# IMX7S_CONNECTORS___IHM.net
KiCad netlist of a schematic drawn in Altium Designer
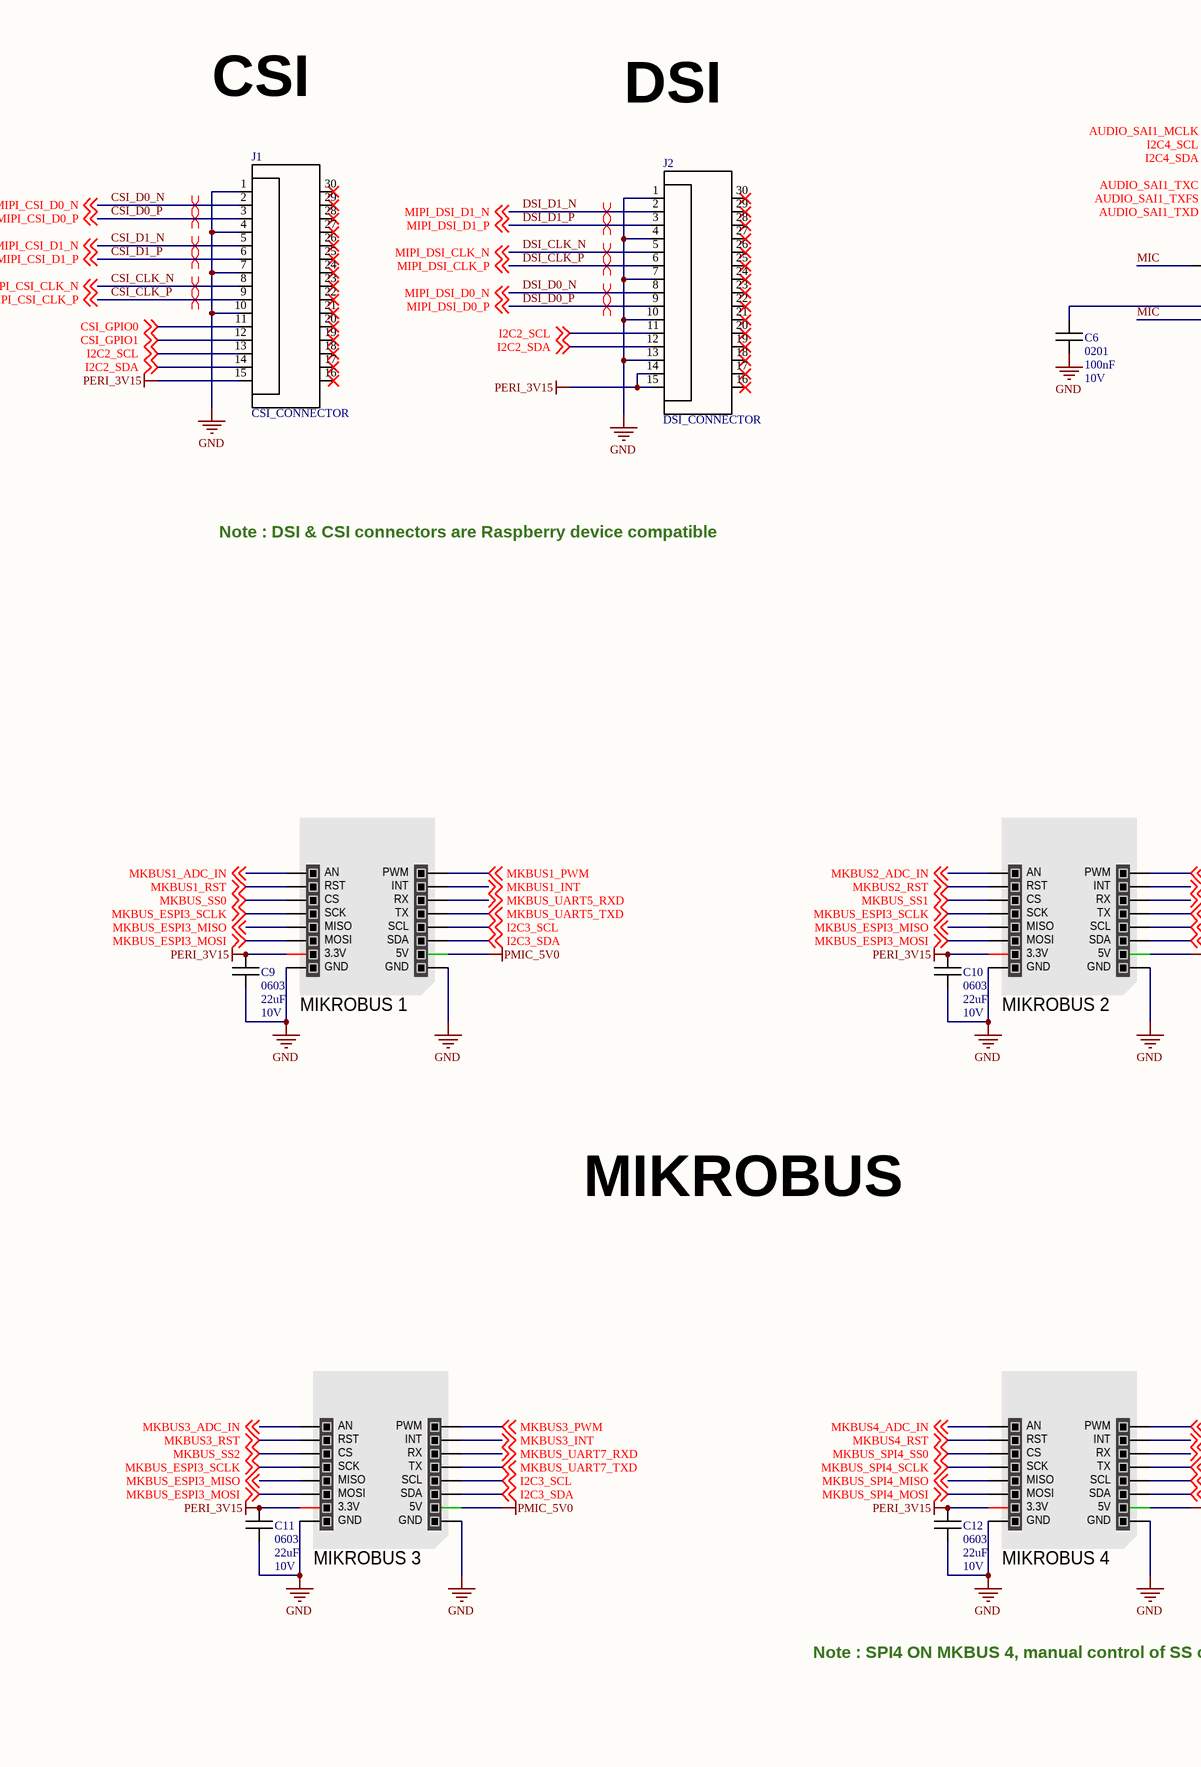
[diagram p0: IMX7S_CONNECTORS_&_IHM.SchDoc, left]
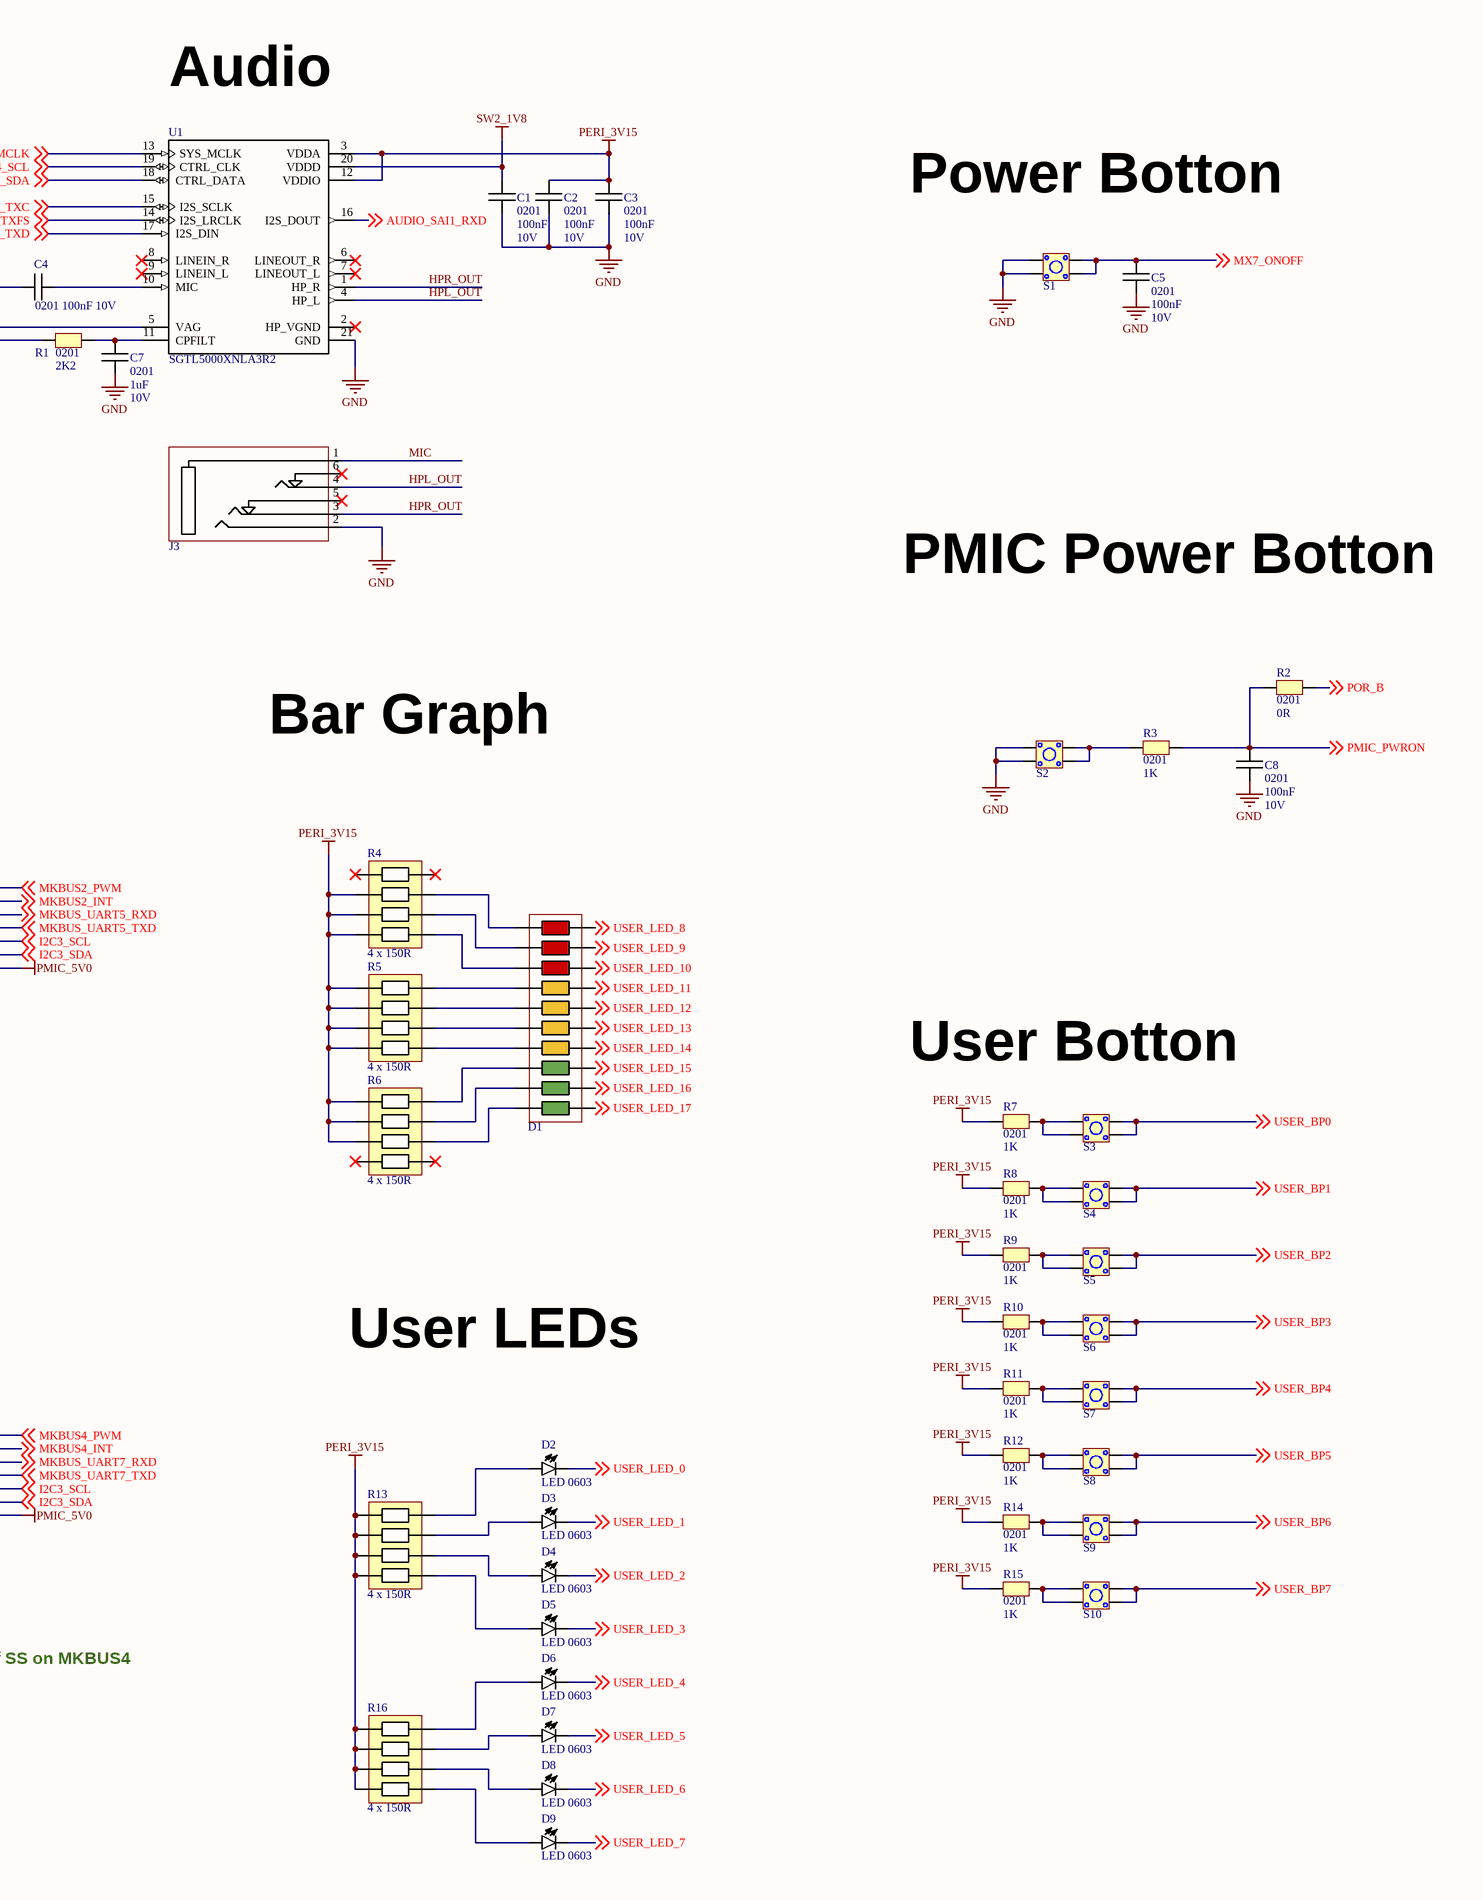
[diagram p1: IMX7S_CONNECTORS_&_IHM.SchDoc, right]

(export (version "E")
  (design (tool "Eeschema 10.0.6"))
  (components
    (comp (ref "C1")
      (value "100nF")
      (footprint "C0201")
      (description "CAP CER 0.1UF 10V X5R 0201")
      (fields
        (field (name "PACKAGE") "0201")
        (field (name "VOLTAGE") "10V")
        (field (name "TOLERANCE") "10%")
        (field (name "Comment") "C0201")
      )
      (libsource (lib "Schlib_IMX7") (part "C0201"))
    )
    (comp (ref "C2")
      (value "100nF")
      (footprint "C0201")
      (description "CAP CER 0.1UF 10V X5R 0201")
      (fields
        (field (name "PACKAGE") "0201")
        (field (name "VOLTAGE") "10V")
        (field (name "TOLERANCE") "10%")
        (field (name "Comment") "C0201")
      )
      (libsource (lib "Schlib_IMX7") (part "C0201"))
    )
    (comp (ref "C3")
      (value "100nF")
      (footprint "C0201")
      (description "CAP CER 0.1UF 10V X5R 0201")
      (fields
        (field (name "PACKAGE") "0201")
        (field (name "VOLTAGE") "10V")
        (field (name "TOLERANCE") "10%")
        (field (name "Comment") "C0201")
      )
      (libsource (lib "Schlib_IMX7") (part "C0201"))
    )
    (comp (ref "C4")
      (value "100nF")
      (footprint "C0201")
      (description "CAP CER 0.1UF 10V X5R 0201")
      (fields
        (field (name "PACKAGE") "0201")
        (field (name "VOLTAGE") "10V")
        (field (name "TOLERANCE") "10%")
        (field (name "Comment") "C0201")
      )
      (libsource (lib "Schlib_IMX7") (part "C0201"))
    )
    (comp (ref "C5")
      (value "100nF")
      (footprint "C0201")
      (description "CAP CER 0.1UF 10V X5R 0201")
      (fields
        (field (name "PACKAGE") "0201")
        (field (name "VOLTAGE") "10V")
        (field (name "TOLERANCE") "10%")
        (field (name "Comment") "C0201")
      )
      (libsource (lib "Schlib_IMX7") (part "C0201"))
    )
    (comp (ref "C6")
      (value "100nF")
      (footprint "C0201")
      (description "CAP CER 0.1UF 10V X5R 0201")
      (fields
        (field (name "PACKAGE") "0201")
        (field (name "VOLTAGE") "10V")
        (field (name "TOLERANCE") "10%")
        (field (name "Comment") "C0201")
      )
      (libsource (lib "Schlib_IMX7") (part "C0201"))
    )
    (comp (ref "C7")
      (value "1uF")
      (footprint "C0201")
      (description "CAP CER 1UF 6.3V X5R 0201")
      (fields
        (field (name "PACKAGE") "0201")
        (field (name "VOLTAGE") "10V")
        (field (name "TOLERANCE") "20%")
        (field (name "Comment") "C0201")
      )
      (libsource (lib "Schlib_IMX7") (part "C0201"))
    )
    (comp (ref "C8")
      (value "100nF")
      (footprint "C0201")
      (description "CAP CER 0.1UF 10V X5R 0201")
      (fields
        (field (name "PACKAGE") "0201")
        (field (name "VOLTAGE") "10V")
        (field (name "TOLERANCE") "10%")
        (field (name "Comment") "C0201")
      )
      (libsource (lib "Schlib_IMX7") (part "C0201"))
    )
    (comp (ref "C9")
      (value "22uF")
      (footprint "C0603")
      (description "Cap Ceramic 22uF 6.3V X5R 20% SMD 0603 85C Paper T/R")
      (fields
        (field (name "PACKAGE") "0603")
        (field (name "VOLTAGE") "10V")
        (field (name "TOLERANCE") "20%")
        (field (name "Comment") "C0603")
      )
      (libsource (lib "Schlib_IMX7") (part "C0603"))
    )
    (comp (ref "C10")
      (value "22uF")
      (footprint "C0603")
      (description "Cap Ceramic 22uF 6.3V X5R 20% SMD 0603 85C Paper T/R")
      (fields
        (field (name "PACKAGE") "0603")
        (field (name "VOLTAGE") "10V")
        (field (name "TOLERANCE") "20%")
        (field (name "Comment") "C0603")
      )
      (libsource (lib "Schlib_IMX7") (part "C0603"))
    )
    (comp (ref "C11")
      (value "22uF")
      (footprint "C0603")
      (description "Cap Ceramic 22uF 6.3V X5R 20% SMD 0603 85C Paper T/R")
      (fields
        (field (name "PACKAGE") "0603")
        (field (name "VOLTAGE") "10V")
        (field (name "TOLERANCE") "20%")
        (field (name "Comment") "C0603")
      )
      (libsource (lib "Schlib_IMX7") (part "C0603"))
    )
    (comp (ref "C12")
      (value "22uF")
      (footprint "C0603")
      (description "Cap Ceramic 22uF 6.3V X5R 20% SMD 0603 85C Paper T/R")
      (fields
        (field (name "PACKAGE") "0603")
        (field (name "VOLTAGE") "10V")
        (field (name "TOLERANCE") "20%")
        (field (name "Comment") "C0603")
      )
      (libsource (lib "Schlib_IMX7") (part "C0603"))
    )
    (comp (ref "D1")
      (value "BARGRAPH")
      (footprint "BARGRAPH")
      (description "BAR GRAPH, 10LED, GREEN/YEL/RED - More Details")
      (libsource (lib "Schlib_IMX7") (part "BARGRAPH"))
    )
    (comp (ref "D2")
      (value "LED 0603")
      (footprint "D0603")
      (description "LED RED DIFFUSED 0603 SMD")
      (libsource (lib "Schlib_IMX7") (part "LED"))
    )
    (comp (ref "D3")
      (value "LED 0603")
      (footprint "D0603")
      (description "LED RED DIFFUSED 0603 SMD")
      (libsource (lib "Schlib_IMX7") (part "LED"))
    )
    (comp (ref "D4")
      (value "LED 0603")
      (footprint "D0603")
      (description "LED RED DIFFUSED 0603 SMD")
      (libsource (lib "Schlib_IMX7") (part "LED"))
    )
    (comp (ref "D5")
      (value "LED 0603")
      (footprint "D0603")
      (description "LED RED DIFFUSED 0603 SMD")
      (libsource (lib "Schlib_IMX7") (part "LED"))
    )
    (comp (ref "D6")
      (value "LED 0603")
      (footprint "D0603")
      (description "LED RED DIFFUSED 0603 SMD")
      (libsource (lib "Schlib_IMX7") (part "LED"))
    )
    (comp (ref "D7")
      (value "LED 0603")
      (footprint "D0603")
      (description "LED RED DIFFUSED 0603 SMD")
      (libsource (lib "Schlib_IMX7") (part "LED"))
    )
    (comp (ref "D8")
      (value "LED 0603")
      (footprint "D0603")
      (description "LED RED DIFFUSED 0603 SMD")
      (libsource (lib "Schlib_IMX7") (part "LED"))
    )
    (comp (ref "D9")
      (value "LED 0603")
      (footprint "D0603")
      (description "LED RED DIFFUSED 0603 SMD")
      (libsource (lib "Schlib_IMX7") (part "LED"))
    )
    (comp (ref "J1")
      (value "CSI_CONNECTOR")
      (footprint "CSI_DSI")
      (libsource (lib "Schlib_IMX7") (part "CSI_DSI_CONN"))
    )
    (comp (ref "J2")
      (value "DSI_CONNECTOR")
      (footprint "CSI_DSI")
      (libsource (lib "Schlib_IMX7") (part "CSI_DSI_CONN"))
    )
    (comp (ref "J3")
      (value "JACK_AUDIO")
      (footprint "JACK_AUDIO")
      (libsource (lib "Schlib_IMX7") (part "JACK_AUDIO"))
    )
    (comp (ref "MIKROBUS 1")
      (value "MIKROBUS HOST CONN.")
      (footprint "MIKROBUS HOST CONN.")
      (description "mikroBUS Host Socket")
      (libsource (lib "Schlib_IMX7") (part "MIKROBUS HOST CONN._1"))
    )
    (comp (ref "MIKROBUS 2")
      (value "MIKROBUS HOST CONN.")
      (footprint "MIKROBUS HOST CONN.")
      (description "mikroBUS Host Socket")
      (libsource (lib "Schlib_IMX7") (part "MIKROBUS HOST CONN._1"))
    )
    (comp (ref "MIKROBUS 3")
      (value "MIKROBUS HOST CONN.")
      (footprint "MIKROBUS HOST CONN.")
      (description "mikroBUS Host Socket")
      (libsource (lib "Schlib_IMX7") (part "MIKROBUS HOST CONN._1"))
    )
    (comp (ref "MIKROBUS 4")
      (value "MIKROBUS HOST CONN.")
      (footprint "MIKROBUS HOST CONN.")
      (description "mikroBUS Host Socket")
      (libsource (lib "Schlib_IMX7") (part "MIKROBUS HOST CONN._1"))
    )
    (comp (ref "R1")
      (value "2K2")
      (footprint "R0201")
      (description "RESISTOR, 0201, 0.05W, 1%, 2K2")
      (fields (field (name "PACKAGE") "0201") (field (name "VOLTAGE") "0V") (field (name "TOLERANCE") "1%"))
      (libsource (lib "Schlib_IMX7") (part "R0201"))
    )
    (comp (ref "R2")
      (value "0R")
      (footprint "R0201")
      (description "RES SMD 0 OHM JUMPER 1/20W 0201")
      (fields (field (name "PACKAGE") "0201") (field (name "VOLTAGE") "0V") (field (name "TOLERANCE") "5%"))
      (libsource (lib "Schlib_IMX7") (part "R0201"))
    )
    (comp (ref "R3")
      (value "1K")
      (footprint "R0201")
      (description "RES SMD 1K OHM 1% 1/20W 0201")
      (fields (field (name "PACKAGE") "0201") (field (name "VOLTAGE") "0V") (field (name "TOLERANCE") "1%"))
      (libsource (lib "Schlib_IMX7") (part "R0201"))
    )
    (comp (ref "R4")
      (value "4 x 150R")
      (footprint "Reseau_R_1206")
      (fields (field (name "TOLERANCE") "5%"))
      (libsource (lib "Schlib_IMX7") (part "Reseau_res"))
    )
    (comp (ref "R5")
      (value "4 x 150R")
      (footprint "Reseau_R_1206")
      (fields (field (name "TOLERANCE") "5%"))
      (libsource (lib "Schlib_IMX7") (part "Reseau_res"))
    )
    (comp (ref "R6")
      (value "4 x 150R")
      (footprint "Reseau_R_1206")
      (fields (field (name "TOLERANCE") "5%"))
      (libsource (lib "Schlib_IMX7") (part "Reseau_res"))
    )
    (comp (ref "R7")
      (value "1K")
      (footprint "R0201")
      (description "RES SMD 1K OHM 1% 1/20W 0201")
      (fields (field (name "PACKAGE") "0201") (field (name "VOLTAGE") "0V") (field (name "TOLERANCE") "1%"))
      (libsource (lib "Schlib_IMX7") (part "R0201"))
    )
    (comp (ref "R8")
      (value "1K")
      (footprint "R0201")
      (description "RES SMD 1K OHM 1% 1/20W 0201")
      (fields (field (name "PACKAGE") "0201") (field (name "VOLTAGE") "0V") (field (name "TOLERANCE") "1%"))
      (libsource (lib "Schlib_IMX7") (part "R0201"))
    )
    (comp (ref "R9")
      (value "1K")
      (footprint "R0201")
      (description "RES SMD 1K OHM 1% 1/20W 0201")
      (fields (field (name "PACKAGE") "0201") (field (name "VOLTAGE") "0V") (field (name "TOLERANCE") "1%"))
      (libsource (lib "Schlib_IMX7") (part "R0201"))
    )
    (comp (ref "R10")
      (value "1K")
      (footprint "R0201")
      (description "RES SMD 1K OHM 1% 1/20W 0201")
      (fields (field (name "PACKAGE") "0201") (field (name "VOLTAGE") "0V") (field (name "TOLERANCE") "1%"))
      (libsource (lib "Schlib_IMX7") (part "R0201"))
    )
    (comp (ref "R11")
      (value "1K")
      (footprint "R0201")
      (description "RES SMD 1K OHM 1% 1/20W 0201")
      (fields (field (name "PACKAGE") "0201") (field (name "VOLTAGE") "0V") (field (name "TOLERANCE") "1%"))
      (libsource (lib "Schlib_IMX7") (part "R0201"))
    )
    (comp (ref "R12")
      (value "1K")
      (footprint "R0201")
      (description "RES SMD 1K OHM 1% 1/20W 0201")
      (fields (field (name "PACKAGE") "0201") (field (name "VOLTAGE") "0V") (field (name "TOLERANCE") "1%"))
      (libsource (lib "Schlib_IMX7") (part "R0201"))
    )
    (comp (ref "R13")
      (value "4 x 150R")
      (footprint "Reseau_R_1206")
      (fields (field (name "TOLERANCE") "5%"))
      (libsource (lib "Schlib_IMX7") (part "Reseau_res"))
    )
    (comp (ref "R14")
      (value "1K")
      (footprint "R0201")
      (description "RES SMD 1K OHM 1% 1/20W 0201")
      (fields (field (name "PACKAGE") "0201") (field (name "VOLTAGE") "0V") (field (name "TOLERANCE") "1%"))
      (libsource (lib "Schlib_IMX7") (part "R0201"))
    )
    (comp (ref "R15")
      (value "1K")
      (footprint "R0201")
      (description "RES SMD 1K OHM 1% 1/20W 0201")
      (fields (field (name "PACKAGE") "0201") (field (name "VOLTAGE") "0V") (field (name "TOLERANCE") "1%"))
      (libsource (lib "Schlib_IMX7") (part "R0201"))
    )
    (comp (ref "R16")
      (value "4 x 150R")
      (footprint "Reseau_R_1206")
      (fields (field (name "TOLERANCE") "5%"))
      (libsource (lib "Schlib_IMX7") (part "Reseau_res"))
    )
    (comp (ref "S1")
      (value "BP")
      (footprint "BP")
      (description "Switch Tactile N.O. SPST Round Button Gull Wing 0.05A 12VDC 100000Cycles 1.6N SMD T/R")
      (fields
        (field (name "MANUFACTURER") "TE Connectivity (Tyco Electronics)")
        (field (name "MANUFACTURER PART NUMBER") "1-1825027-4")
      )
      (libsource (lib "Schlib_IMX7") (part "BP"))
    )
    (comp (ref "S2")
      (value "BP")
      (footprint "BP")
      (description "Switch Tactile N.O. SPST Round Button Gull Wing 0.05A 12VDC 100000Cycles 1.6N SMD T/R")
      (fields
        (field (name "MANUFACTURER") "TE Connectivity (Tyco Electronics)")
        (field (name "MANUFACTURER PART NUMBER") "1-1825027-4")
      )
      (libsource (lib "Schlib_IMX7") (part "BP"))
    )
    (comp (ref "S3")
      (value "BP")
      (footprint "BP")
      (description "Switch Tactile N.O. SPST Round Button Gull Wing 0.05A 12VDC 100000Cycles 1.6N SMD T/R")
      (fields
        (field (name "MANUFACTURER") "TE Connectivity (Tyco Electronics)")
        (field (name "MANUFACTURER PART NUMBER") "1-1825027-4")
      )
      (libsource (lib "Schlib_IMX7") (part "BP"))
    )
    (comp (ref "S4")
      (value "BP")
      (footprint "BP")
      (description "Switch Tactile N.O. SPST Round Button Gull Wing 0.05A 12VDC 100000Cycles 1.6N SMD T/R")
      (fields
        (field (name "MANUFACTURER") "TE Connectivity (Tyco Electronics)")
        (field (name "MANUFACTURER PART NUMBER") "1-1825027-4")
      )
      (libsource (lib "Schlib_IMX7") (part "BP"))
    )
    (comp (ref "S5")
      (value "BP")
      (footprint "BP")
      (description "Switch Tactile N.O. SPST Round Button Gull Wing 0.05A 12VDC 100000Cycles 1.6N SMD T/R")
      (fields
        (field (name "MANUFACTURER") "TE Connectivity (Tyco Electronics)")
        (field (name "MANUFACTURER PART NUMBER") "1-1825027-4")
      )
      (libsource (lib "Schlib_IMX7") (part "BP"))
    )
    (comp (ref "S6")
      (value "BP")
      (footprint "BP")
      (description "Switch Tactile N.O. SPST Round Button Gull Wing 0.05A 12VDC 100000Cycles 1.6N SMD T/R")
      (fields
        (field (name "MANUFACTURER") "TE Connectivity (Tyco Electronics)")
        (field (name "MANUFACTURER PART NUMBER") "1-1825027-4")
      )
      (libsource (lib "Schlib_IMX7") (part "BP"))
    )
    (comp (ref "S7")
      (value "BP")
      (footprint "BP")
      (description "Switch Tactile N.O. SPST Round Button Gull Wing 0.05A 12VDC 100000Cycles 1.6N SMD T/R")
      (fields
        (field (name "MANUFACTURER") "TE Connectivity (Tyco Electronics)")
        (field (name "MANUFACTURER PART NUMBER") "1-1825027-4")
      )
      (libsource (lib "Schlib_IMX7") (part "BP"))
    )
    (comp (ref "S8")
      (value "BP")
      (footprint "BP")
      (description "Switch Tactile N.O. SPST Round Button Gull Wing 0.05A 12VDC 100000Cycles 1.6N SMD T/R")
      (fields
        (field (name "MANUFACTURER") "TE Connectivity (Tyco Electronics)")
        (field (name "MANUFACTURER PART NUMBER") "1-1825027-4")
      )
      (libsource (lib "Schlib_IMX7") (part "BP"))
    )
    (comp (ref "S9")
      (value "BP")
      (footprint "BP")
      (description "Switch Tactile N.O. SPST Round Button Gull Wing 0.05A 12VDC 100000Cycles 1.6N SMD T/R")
      (fields
        (field (name "MANUFACTURER") "TE Connectivity (Tyco Electronics)")
        (field (name "MANUFACTURER PART NUMBER") "1-1825027-4")
      )
      (libsource (lib "Schlib_IMX7") (part "BP"))
    )
    (comp (ref "S10")
      (value "BP")
      (footprint "BP")
      (description "Switch Tactile N.O. SPST Round Button Gull Wing 0.05A 12VDC 100000Cycles 1.6N SMD T/R")
      (fields
        (field (name "MANUFACTURER") "TE Connectivity (Tyco Electronics)")
        (field (name "MANUFACTURER PART NUMBER") "1-1825027-4")
      )
      (libsource (lib "Schlib_IMX7") (part "BP"))
    )
    (comp (ref "U1")
      (value "SGTL5000XNLA3R2")
      (footprint "QFN40P300X300X60-21N")
      (description "Audio Codec , Ultra Low-Power, 4 mw for DAC-to-HP, 98 dB SNR and -80 dB THD+N, QFN 32, Reel")
      (fields (field (name "DIGI-KEY_PART_NUMBER") "568-13255-1-ND") (field (name "MF") "NXP USA"))
      (libsource (lib "Schlib_IMX7") (part "SGTL5000XNLA3R2"))
    )
  )
  (nets
    (net (code "1") (name "/HPL_OUT") (class "Default")
      (node (ref "J3") (pin "4") (pintype "passive"))
      (node (ref "U1") (pin "4") (pinfunction "HP_L_4") (pintype "output"))
    )
    (net (code "2") (name "/HPR_OUT") (class "Default")
      (node (ref "J3") (pin "3") (pintype "passive"))
      (node (ref "U1") (pin "1") (pinfunction "HP_R_1") (pintype "output"))
    )
    (net (code "3") (name "/MIC") (class "Default")
      (node (ref "C4") (pin "1") (pinfunction "1_1") (pintype "passive"))
      (node (ref "J3") (pin "1") (pintype "passive"))
      (node (ref "R1") (pin "1") (pinfunction "1_1") (pintype "passive"))
    )
    (net (code "4") (name "AUDIO_SAI1_MCLK") (class "Default")
      (node (ref "U1") (pin "13") (pinfunction "SYS_MCLK_13") (pintype "input"))
    )
    (net (code "5") (name "AUDIO_SAI1_RXD") (class "Default")
      (node (ref "U1") (pin "16") (pinfunction "I2S_DOUT_16") (pintype "output"))
    )
    (net (code "6") (name "AUDIO_SAI1_TXC") (class "Default")
      (node (ref "U1") (pin "15") (pinfunction "I2S_SCLK_15") (pintype "bidirectional"))
    )
    (net (code "7") (name "AUDIO_SAI1_TXD") (class "Default")
      (node (ref "U1") (pin "17") (pinfunction "I2S_DIN_17") (pintype "input"))
    )
    (net (code "8") (name "AUDIO_SAI1_TXFS") (class "Default")
      (node (ref "U1") (pin "14") (pinfunction "I2S_LRCLK_14") (pintype "bidirectional"))
    )
    (net (code "9") (name "CSI_GPIO0") (class "Default")
      (node (ref "J1") (pin "11") (pinfunction "11_11") (pintype "passive"))
    )
    (net (code "10") (name "CSI_GPIO1") (class "Default")
      (node (ref "J1") (pin "12") (pinfunction "12_12") (pintype "passive"))
    )
    (net (code "11") (name "GND") (class "Default")
      (node (ref "C1") (pin "1") (pinfunction "1_1") (pintype "passive"))
      (node (ref "C10") (pin "1") (pinfunction "1_1") (pintype "passive"))
      (node (ref "C11") (pin "1") (pinfunction "1_1") (pintype "passive"))
      (node (ref "C12") (pin "1") (pinfunction "1_1") (pintype "passive"))
      (node (ref "C2") (pin "1") (pinfunction "1_1") (pintype "passive"))
      (node (ref "C3") (pin "1") (pinfunction "1_1") (pintype "passive"))
      (node (ref "C5") (pin "1") (pinfunction "1_1") (pintype "passive"))
      (node (ref "C6") (pin "1") (pinfunction "1_1") (pintype "passive"))
      (node (ref "C7") (pin "1") (pinfunction "1_1") (pintype "passive"))
      (node (ref "C8") (pin "1") (pinfunction "1_1") (pintype "passive"))
      (node (ref "C9") (pin "1") (pinfunction "1_1") (pintype "passive"))
      (node (ref "J1") (pin "1") (pinfunction "1_1") (pintype "passive"))
      (node (ref "J1") (pin "10") (pinfunction "10_10") (pintype "passive"))
      (node (ref "J1") (pin "4") (pinfunction "4_4") (pintype "passive"))
      (node (ref "J1") (pin "7") (pinfunction "7_7") (pintype "passive"))
      (node (ref "J2") (pin "1") (pinfunction "1_1") (pintype "passive"))
      (node (ref "J2") (pin "10") (pinfunction "10_10") (pintype "passive"))
      (node (ref "J2") (pin "13") (pinfunction "13_13") (pintype "passive"))
      (node (ref "J2") (pin "4") (pinfunction "4_4") (pintype "passive"))
      (node (ref "J2") (pin "7") (pinfunction "7_7") (pintype "passive"))
      (node (ref "J3") (pin "2") (pintype "passive"))
      (node (ref "MIKROBUS 1") (pin "8") (pinfunction "GND_8") (pintype "passive"))
      (node (ref "MIKROBUS 1") (pin "9") (pinfunction "GND_9") (pintype "passive"))
      (node (ref "MIKROBUS 2") (pin "8") (pinfunction "GND_8") (pintype "passive"))
      (node (ref "MIKROBUS 2") (pin "9") (pinfunction "GND_9") (pintype "passive"))
      (node (ref "MIKROBUS 3") (pin "8") (pinfunction "GND_8") (pintype "passive"))
      (node (ref "MIKROBUS 3") (pin "9") (pinfunction "GND_9") (pintype "passive"))
      (node (ref "MIKROBUS 4") (pin "8") (pinfunction "GND_8") (pintype "passive"))
      (node (ref "MIKROBUS 4") (pin "9") (pinfunction "GND_9") (pintype "passive"))
      (node (ref "S1") (pin "1") (pinfunction "1_1") (pintype "passive"))
      (node (ref "S1") (pin "2") (pinfunction "2_2") (pintype "passive"))
      (node (ref "S2") (pin "1") (pinfunction "1_1") (pintype "passive"))
      (node (ref "S2") (pin "2") (pinfunction "2_2") (pintype "passive"))
      (node (ref "U1") (pin "21") (pinfunction "GND_21") (pintype "power_in"))
    )
    (net (code "12") (name "I2C2_SCL") (class "Default")
      (node (ref "J1") (pin "13") (pinfunction "13_13") (pintype "passive"))
      (node (ref "J2") (pin "11") (pinfunction "11_11") (pintype "passive"))
    )
    (net (code "13") (name "I2C2_SDA") (class "Default")
      (node (ref "J1") (pin "14") (pinfunction "14_14") (pintype "passive"))
      (node (ref "J2") (pin "12") (pinfunction "12_12") (pintype "passive"))
    )
    (net (code "14") (name "I2C3_SCL") (class "Default")
      (node (ref "MIKROBUS 1") (pin "12") (pinfunction "SCL_12") (pintype "passive"))
      (node (ref "MIKROBUS 2") (pin "12") (pinfunction "SCL_12") (pintype "passive"))
      (node (ref "MIKROBUS 3") (pin "12") (pinfunction "SCL_12") (pintype "passive"))
      (node (ref "MIKROBUS 4") (pin "12") (pinfunction "SCL_12") (pintype "passive"))
    )
    (net (code "15") (name "I2C3_SDA") (class "Default")
      (node (ref "MIKROBUS 1") (pin "11") (pinfunction "SDA_11") (pintype "passive"))
      (node (ref "MIKROBUS 2") (pin "11") (pinfunction "SDA_11") (pintype "passive"))
      (node (ref "MIKROBUS 3") (pin "11") (pinfunction "SDA_11") (pintype "passive"))
      (node (ref "MIKROBUS 4") (pin "11") (pinfunction "SDA_11") (pintype "passive"))
    )
    (net (code "16") (name "I2C4_SCL") (class "Default")
      (node (ref "U1") (pin "19") (pinfunction "CTRL_CLK_19") (pintype "bidirectional"))
    )
    (net (code "17") (name "I2C4_SDA") (class "Default")
      (node (ref "U1") (pin "18") (pinfunction "CTRL_DATA_18") (pintype "bidirectional"))
    )
    (net (code "18") (name "MIPI_CSI_CLK_N") (class "Default")
      (node (ref "J1") (pin "8") (pinfunction "8_8") (pintype "passive"))
    )
    (net (code "19") (name "MIPI_CSI_CLK_P") (class "Default")
      (node (ref "J1") (pin "9") (pinfunction "9_9") (pintype "passive"))
    )
    (net (code "20") (name "MIPI_CSI_D0_N") (class "Default")
      (node (ref "J1") (pin "2") (pinfunction "2_2") (pintype "passive"))
    )
    (net (code "21") (name "MIPI_CSI_D0_P") (class "Default")
      (node (ref "J1") (pin "3") (pinfunction "3_3") (pintype "passive"))
    )
    (net (code "22") (name "MIPI_CSI_D1_N") (class "Default")
      (node (ref "J1") (pin "5") (pinfunction "5_5") (pintype "passive"))
    )
    (net (code "23") (name "MIPI_CSI_D1_P") (class "Default")
      (node (ref "J1") (pin "6") (pinfunction "6_6") (pintype "passive"))
    )
    (net (code "24") (name "MIPI_DSI_CLK_N") (class "Default")
      (node (ref "J2") (pin "5") (pinfunction "5_5") (pintype "passive"))
    )
    (net (code "25") (name "MIPI_DSI_CLK_P") (class "Default")
      (node (ref "J2") (pin "6") (pinfunction "6_6") (pintype "passive"))
    )
    (net (code "26") (name "MIPI_DSI_D0_N") (class "Default")
      (node (ref "J2") (pin "8") (pinfunction "8_8") (pintype "passive"))
    )
    (net (code "27") (name "MIPI_DSI_D0_P") (class "Default")
      (node (ref "J2") (pin "9") (pinfunction "9_9") (pintype "passive"))
    )
    (net (code "28") (name "MIPI_DSI_D1_N") (class "Default")
      (node (ref "J2") (pin "2") (pinfunction "2_2") (pintype "passive"))
    )
    (net (code "29") (name "MIPI_DSI_D1_P") (class "Default")
      (node (ref "J2") (pin "3") (pinfunction "3_3") (pintype "passive"))
    )
    (net (code "30") (name "MKBUS1_ADC_IN") (class "Default")
      (node (ref "MIKROBUS 1") (pin "1") (pinfunction "AN_1") (pintype "passive"))
    )
    (net (code "31") (name "MKBUS1_INT") (class "Default")
      (node (ref "MIKROBUS 1") (pin "15") (pinfunction "INT_15") (pintype "passive"))
    )
    (net (code "32") (name "MKBUS1_PWM") (class "Default")
      (node (ref "MIKROBUS 1") (pin "16") (pinfunction "PWM_16") (pintype "passive"))
    )
    (net (code "33") (name "MKBUS1_RST") (class "Default")
      (node (ref "MIKROBUS 1") (pin "2") (pinfunction "RST_2") (pintype "passive"))
    )
    (net (code "34") (name "MKBUS2_ADC_IN") (class "Default")
      (node (ref "MIKROBUS 2") (pin "1") (pinfunction "AN_1") (pintype "passive"))
    )
    (net (code "35") (name "MKBUS2_INT") (class "Default")
      (node (ref "MIKROBUS 2") (pin "15") (pinfunction "INT_15") (pintype "passive"))
    )
    (net (code "36") (name "MKBUS2_PWM") (class "Default")
      (node (ref "MIKROBUS 2") (pin "16") (pinfunction "PWM_16") (pintype "passive"))
    )
    (net (code "37") (name "MKBUS2_RST") (class "Default")
      (node (ref "MIKROBUS 2") (pin "2") (pinfunction "RST_2") (pintype "passive"))
    )
    (net (code "38") (name "MKBUS3_ADC_IN") (class "Default")
      (node (ref "MIKROBUS 3") (pin "1") (pinfunction "AN_1") (pintype "passive"))
    )
    (net (code "39") (name "MKBUS3_INT") (class "Default")
      (node (ref "MIKROBUS 3") (pin "15") (pinfunction "INT_15") (pintype "passive"))
    )
    (net (code "40") (name "MKBUS3_PWM") (class "Default")
      (node (ref "MIKROBUS 3") (pin "16") (pinfunction "PWM_16") (pintype "passive"))
    )
    (net (code "41") (name "MKBUS3_RST") (class "Default")
      (node (ref "MIKROBUS 3") (pin "2") (pinfunction "RST_2") (pintype "passive"))
    )
    (net (code "42") (name "MKBUS4_ADC_IN") (class "Default")
      (node (ref "MIKROBUS 4") (pin "1") (pinfunction "AN_1") (pintype "passive"))
    )
    (net (code "43") (name "MKBUS4_INT") (class "Default")
      (node (ref "MIKROBUS 4") (pin "15") (pinfunction "INT_15") (pintype "passive"))
    )
    (net (code "44") (name "MKBUS4_PWM") (class "Default")
      (node (ref "MIKROBUS 4") (pin "16") (pinfunction "PWM_16") (pintype "passive"))
    )
    (net (code "45") (name "MKBUS4_RST") (class "Default")
      (node (ref "MIKROBUS 4") (pin "2") (pinfunction "RST_2") (pintype "passive"))
    )
    (net (code "46") (name "MKBUS_ESPI3_MISO") (class "Default")
      (node (ref "MIKROBUS 1") (pin "5") (pinfunction "MISO_5") (pintype "passive"))
      (node (ref "MIKROBUS 2") (pin "5") (pinfunction "MISO_5") (pintype "passive"))
      (node (ref "MIKROBUS 3") (pin "5") (pinfunction "MISO_5") (pintype "passive"))
    )
    (net (code "47") (name "MKBUS_ESPI3_MOSI") (class "Default")
      (node (ref "MIKROBUS 1") (pin "6") (pinfunction "MOSI_6") (pintype "passive"))
      (node (ref "MIKROBUS 2") (pin "6") (pinfunction "MOSI_6") (pintype "passive"))
      (node (ref "MIKROBUS 3") (pin "6") (pinfunction "MOSI_6") (pintype "passive"))
    )
    (net (code "48") (name "MKBUS_ESPI3_SCLK") (class "Default")
      (node (ref "MIKROBUS 1") (pin "4") (pinfunction "SCK_4") (pintype "passive"))
      (node (ref "MIKROBUS 2") (pin "4") (pinfunction "SCK_4") (pintype "passive"))
      (node (ref "MIKROBUS 3") (pin "4") (pinfunction "SCK_4") (pintype "passive"))
    )
    (net (code "49") (name "MKBUS_SPI4_MISO") (class "Default")
      (node (ref "MIKROBUS 4") (pin "5") (pinfunction "MISO_5") (pintype "passive"))
    )
    (net (code "50") (name "MKBUS_SPI4_MOSI") (class "Default")
      (node (ref "MIKROBUS 4") (pin "6") (pinfunction "MOSI_6") (pintype "passive"))
    )
    (net (code "51") (name "MKBUS_SPI4_SCLK") (class "Default")
      (node (ref "MIKROBUS 4") (pin "4") (pinfunction "SCK_4") (pintype "passive"))
    )
    (net (code "52") (name "MKBUS_SPI4_SS0") (class "Default")
      (node (ref "MIKROBUS 4") (pin "3") (pinfunction "CS_3") (pintype "passive"))
    )
    (net (code "53") (name "MKBUS_SS0") (class "Default")
      (node (ref "MIKROBUS 1") (pin "3") (pinfunction "CS_3") (pintype "passive"))
    )
    (net (code "54") (name "MKBUS_SS1") (class "Default")
      (node (ref "MIKROBUS 2") (pin "3") (pinfunction "CS_3") (pintype "passive"))
    )
    (net (code "55") (name "MKBUS_SS2") (class "Default")
      (node (ref "MIKROBUS 3") (pin "3") (pinfunction "CS_3") (pintype "passive"))
    )
    (net (code "56") (name "MKBUS_UART5_RXD") (class "Default")
      (node (ref "MIKROBUS 1") (pin "14") (pinfunction "RX_14") (pintype "passive"))
      (node (ref "MIKROBUS 2") (pin "14") (pinfunction "RX_14") (pintype "passive"))
    )
    (net (code "57") (name "MKBUS_UART5_TXD") (class "Default")
      (node (ref "MIKROBUS 1") (pin "13") (pinfunction "TX_13") (pintype "passive"))
      (node (ref "MIKROBUS 2") (pin "13") (pinfunction "TX_13") (pintype "passive"))
    )
    (net (code "58") (name "MKBUS_UART7_RXD") (class "Default")
      (node (ref "MIKROBUS 3") (pin "14") (pinfunction "RX_14") (pintype "passive"))
      (node (ref "MIKROBUS 4") (pin "14") (pinfunction "RX_14") (pintype "passive"))
    )
    (net (code "59") (name "MKBUS_UART7_TXD") (class "Default")
      (node (ref "MIKROBUS 3") (pin "13") (pinfunction "TX_13") (pintype "passive"))
      (node (ref "MIKROBUS 4") (pin "13") (pinfunction "TX_13") (pintype "passive"))
    )
    (net (code "60") (name "MX7_ONOFF") (class "Default")
      (node (ref "C5") (pin "2") (pinfunction "2_2") (pintype "passive"))
      (node (ref "S1") (pin "3") (pinfunction "3_3") (pintype "passive"))
      (node (ref "S1") (pin "4") (pinfunction "4_4") (pintype "passive"))
    )
    (net (code "61") (name "Net-(D1-Pad1)") (class "Default")
      (node (ref "D1") (pin "1") (pinfunction "1_1") (pintype "passive"))
      (node (ref "R4") (pin "7") (pinfunction "7_7") (pintype "passive"))
    )
    (net (code "62") (name "Net-(D1-Pad2)") (class "Default")
      (node (ref "D1") (pin "2") (pinfunction "2_2") (pintype "passive"))
      (node (ref "R4") (pin "6") (pinfunction "6_6") (pintype "passive"))
    )
    (net (code "63") (name "Net-(D1-Pad3)") (class "Default")
      (node (ref "D1") (pin "3") (pinfunction "3_3") (pintype "passive"))
      (node (ref "R4") (pin "5") (pinfunction "5_5") (pintype "passive"))
    )
    (net (code "64") (name "Net-(D1-Pad4)") (class "Default")
      (node (ref "D1") (pin "4") (pinfunction "4_4") (pintype "passive"))
      (node (ref "R5") (pin "8") (pinfunction "8_8") (pintype "passive"))
    )
    (net (code "65") (name "Net-(D1-Pad5)") (class "Default")
      (node (ref "D1") (pin "5") (pinfunction "5_5") (pintype "passive"))
      (node (ref "R5") (pin "7") (pinfunction "7_7") (pintype "passive"))
    )
    (net (code "66") (name "Net-(D1-Pad6)") (class "Default")
      (node (ref "D1") (pin "6") (pinfunction "6_6") (pintype "passive"))
      (node (ref "R5") (pin "6") (pinfunction "6_6") (pintype "passive"))
    )
    (net (code "67") (name "Net-(D1-Pad7)") (class "Default")
      (node (ref "D1") (pin "7") (pinfunction "7_7") (pintype "passive"))
      (node (ref "R5") (pin "5") (pinfunction "5_5") (pintype "passive"))
    )
    (net (code "68") (name "Net-(D1-Pad8)") (class "Default")
      (node (ref "D1") (pin "8") (pinfunction "8_8") (pintype "passive"))
      (node (ref "R6") (pin "8") (pinfunction "8_8") (pintype "passive"))
    )
    (net (code "69") (name "Net-(D1-Pad9)") (class "Default")
      (node (ref "D1") (pin "9") (pinfunction "9_9") (pintype "passive"))
      (node (ref "R6") (pin "7") (pinfunction "7_7") (pintype "passive"))
    )
    (net (code "70") (name "Net-(D1-Pad10)") (class "Default")
      (node (ref "D1") (pin "10") (pinfunction "10_10") (pintype "passive"))
      (node (ref "R6") (pin "6") (pinfunction "6_6") (pintype "passive"))
    )
    (net (code "71") (name "Net-(D2-A)") (class "Default")
      (node (ref "D2") (pin "1") (pinfunction "A_1") (pintype "passive"))
      (node (ref "R13") (pin "8") (pinfunction "8_8") (pintype "passive"))
    )
    (net (code "72") (name "Net-(D3-A)") (class "Default")
      (node (ref "D3") (pin "1") (pinfunction "A_1") (pintype "passive"))
      (node (ref "R13") (pin "7") (pinfunction "7_7") (pintype "passive"))
    )
    (net (code "73") (name "Net-(D4-A)") (class "Default")
      (node (ref "D4") (pin "1") (pinfunction "A_1") (pintype "passive"))
      (node (ref "R13") (pin "6") (pinfunction "6_6") (pintype "passive"))
    )
    (net (code "74") (name "Net-(D5-A)") (class "Default")
      (node (ref "D5") (pin "1") (pinfunction "A_1") (pintype "passive"))
      (node (ref "R13") (pin "5") (pinfunction "5_5") (pintype "passive"))
    )
    (net (code "75") (name "Net-(D6-A)") (class "Default")
      (node (ref "D6") (pin "1") (pinfunction "A_1") (pintype "passive"))
      (node (ref "R16") (pin "8") (pinfunction "8_8") (pintype "passive"))
    )
    (net (code "76") (name "Net-(D7-A)") (class "Default")
      (node (ref "D7") (pin "1") (pinfunction "A_1") (pintype "passive"))
      (node (ref "R16") (pin "7") (pinfunction "7_7") (pintype "passive"))
    )
    (net (code "77") (name "Net-(D8-A)") (class "Default")
      (node (ref "D8") (pin "1") (pinfunction "A_1") (pintype "passive"))
      (node (ref "R16") (pin "6") (pinfunction "6_6") (pintype "passive"))
    )
    (net (code "78") (name "Net-(D9-A)") (class "Default")
      (node (ref "D9") (pin "1") (pinfunction "A_1") (pintype "passive"))
      (node (ref "R16") (pin "5") (pinfunction "5_5") (pintype "passive"))
    )
    (net (code "79") (name "Net-(R3-Pad1)") (class "Default")
      (node (ref "R3") (pin "1") (pinfunction "1_1") (pintype "passive"))
      (node (ref "S2") (pin "3") (pinfunction "3_3") (pintype "passive"))
      (node (ref "S2") (pin "4") (pinfunction "4_4") (pintype "passive"))
    )
    (net (code "80") (name "Net-(R7-Pad2)") (class "Default")
      (node (ref "R7") (pin "2") (pinfunction "2_2") (pintype "passive"))
      (node (ref "S3") (pin "1") (pinfunction "1_1") (pintype "passive"))
      (node (ref "S3") (pin "2") (pinfunction "2_2") (pintype "passive"))
    )
    (net (code "81") (name "Net-(R8-Pad2)") (class "Default")
      (node (ref "R8") (pin "2") (pinfunction "2_2") (pintype "passive"))
      (node (ref "S4") (pin "1") (pinfunction "1_1") (pintype "passive"))
      (node (ref "S4") (pin "2") (pinfunction "2_2") (pintype "passive"))
    )
    (net (code "82") (name "Net-(R9-Pad2)") (class "Default")
      (node (ref "R9") (pin "2") (pinfunction "2_2") (pintype "passive"))
      (node (ref "S5") (pin "1") (pinfunction "1_1") (pintype "passive"))
      (node (ref "S5") (pin "2") (pinfunction "2_2") (pintype "passive"))
    )
    (net (code "83") (name "Net-(R10-Pad2)") (class "Default")
      (node (ref "R10") (pin "2") (pinfunction "2_2") (pintype "passive"))
      (node (ref "S6") (pin "1") (pinfunction "1_1") (pintype "passive"))
      (node (ref "S6") (pin "2") (pinfunction "2_2") (pintype "passive"))
    )
    (net (code "84") (name "Net-(R11-Pad2)") (class "Default")
      (node (ref "R11") (pin "2") (pinfunction "2_2") (pintype "passive"))
      (node (ref "S7") (pin "1") (pinfunction "1_1") (pintype "passive"))
      (node (ref "S7") (pin "2") (pinfunction "2_2") (pintype "passive"))
    )
    (net (code "85") (name "Net-(R12-Pad2)") (class "Default")
      (node (ref "R12") (pin "2") (pinfunction "2_2") (pintype "passive"))
      (node (ref "S8") (pin "1") (pinfunction "1_1") (pintype "passive"))
      (node (ref "S8") (pin "2") (pinfunction "2_2") (pintype "passive"))
    )
    (net (code "86") (name "Net-(R14-Pad2)") (class "Default")
      (node (ref "R14") (pin "2") (pinfunction "2_2") (pintype "passive"))
      (node (ref "S9") (pin "1") (pinfunction "1_1") (pintype "passive"))
      (node (ref "S9") (pin "2") (pinfunction "2_2") (pintype "passive"))
    )
    (net (code "87") (name "Net-(R15-Pad2)") (class "Default")
      (node (ref "R15") (pin "2") (pinfunction "2_2") (pintype "passive"))
      (node (ref "S10") (pin "1") (pinfunction "1_1") (pintype "passive"))
      (node (ref "S10") (pin "2") (pinfunction "2_2") (pintype "passive"))
    )
    (net (code "88") (name "Net-(U1-CPFILT)") (class "Default")
      (node (ref "C7") (pin "2") (pinfunction "2_2") (pintype "passive"))
      (node (ref "R1") (pin "2") (pinfunction "2_2") (pintype "passive"))
      (node (ref "U1") (pin "11") (pinfunction "CPFILT_11") (pintype "passive"))
    )
    (net (code "89") (name "Net-(U1-MIC)") (class "Default")
      (node (ref "C4") (pin "2") (pinfunction "2_2") (pintype "passive"))
      (node (ref "U1") (pin "10") (pinfunction "MIC_10") (pintype "input"))
    )
    (net (code "90") (name "Net-(U1-VAG)") (class "Default")
      (node (ref "C6") (pin "2") (pinfunction "2_2") (pintype "passive"))
      (node (ref "U1") (pin "5") (pinfunction "VAG_5") (pintype "passive"))
    )
    (net (code "91") (name "PERI_3V15") (class "Default")
      (node (ref "C10") (pin "2") (pinfunction "2_2") (pintype "passive"))
      (node (ref "C11") (pin "2") (pinfunction "2_2") (pintype "passive"))
      (node (ref "C12") (pin "2") (pinfunction "2_2") (pintype "passive"))
      (node (ref "C2") (pin "2") (pinfunction "2_2") (pintype "passive"))
      (node (ref "C3") (pin "2") (pinfunction "2_2") (pintype "passive"))
      (node (ref "C9") (pin "2") (pinfunction "2_2") (pintype "passive"))
      (node (ref "J1") (pin "15") (pinfunction "15_15") (pintype "passive"))
      (node (ref "J2") (pin "14") (pinfunction "14_14") (pintype "passive"))
      (node (ref "J2") (pin "15") (pinfunction "15_15") (pintype "passive"))
      (node (ref "MIKROBUS 1") (pin "7") (pinfunction "3.3V_7") (pintype "passive"))
      (node (ref "MIKROBUS 2") (pin "7") (pinfunction "3.3V_7") (pintype "passive"))
      (node (ref "MIKROBUS 3") (pin "7") (pinfunction "3.3V_7") (pintype "passive"))
      (node (ref "MIKROBUS 4") (pin "7") (pinfunction "3.3V_7") (pintype "passive"))
      (node (ref "R10") (pin "1") (pinfunction "1_1") (pintype "passive"))
      (node (ref "R11") (pin "1") (pinfunction "1_1") (pintype "passive"))
      (node (ref "R12") (pin "1") (pinfunction "1_1") (pintype "passive"))
      (node (ref "R13") (pin "1") (pinfunction "1_1") (pintype "passive"))
      (node (ref "R13") (pin "2") (pinfunction "2_2") (pintype "passive"))
      (node (ref "R13") (pin "3") (pinfunction "3_3") (pintype "passive"))
      (node (ref "R13") (pin "4") (pinfunction "4_4") (pintype "passive"))
      (node (ref "R14") (pin "1") (pinfunction "1_1") (pintype "passive"))
      (node (ref "R15") (pin "1") (pinfunction "1_1") (pintype "passive"))
      (node (ref "R16") (pin "1") (pinfunction "1_1") (pintype "passive"))
      (node (ref "R16") (pin "2") (pinfunction "2_2") (pintype "passive"))
      (node (ref "R16") (pin "3") (pinfunction "3_3") (pintype "passive"))
      (node (ref "R16") (pin "4") (pinfunction "4_4") (pintype "passive"))
      (node (ref "R4") (pin "2") (pinfunction "2_2") (pintype "passive"))
      (node (ref "R4") (pin "3") (pinfunction "3_3") (pintype "passive"))
      (node (ref "R4") (pin "4") (pinfunction "4_4") (pintype "passive"))
      (node (ref "R5") (pin "1") (pinfunction "1_1") (pintype "passive"))
      (node (ref "R5") (pin "2") (pinfunction "2_2") (pintype "passive"))
      (node (ref "R5") (pin "3") (pinfunction "3_3") (pintype "passive"))
      (node (ref "R5") (pin "4") (pinfunction "4_4") (pintype "passive"))
      (node (ref "R6") (pin "1") (pinfunction "1_1") (pintype "passive"))
      (node (ref "R6") (pin "2") (pinfunction "2_2") (pintype "passive"))
      (node (ref "R6") (pin "3") (pinfunction "3_3") (pintype "passive"))
      (node (ref "R7") (pin "1") (pinfunction "1_1") (pintype "passive"))
      (node (ref "R8") (pin "1") (pinfunction "1_1") (pintype "passive"))
      (node (ref "R9") (pin "1") (pinfunction "1_1") (pintype "passive"))
      (node (ref "U1") (pin "12") (pinfunction "VDDIO_12") (pintype "power_in"))
      (node (ref "U1") (pin "3") (pinfunction "VDDA_3") (pintype "power_in"))
    )
    (net (code "92") (name "PMIC_5V0") (class "Default")
      (node (ref "MIKROBUS 1") (pin "10") (pinfunction "5V_10") (pintype "passive"))
      (node (ref "MIKROBUS 2") (pin "10") (pinfunction "5V_10") (pintype "passive"))
      (node (ref "MIKROBUS 3") (pin "10") (pinfunction "5V_10") (pintype "passive"))
      (node (ref "MIKROBUS 4") (pin "10") (pinfunction "5V_10") (pintype "passive"))
    )
    (net (code "93") (name "PMIC_PWRON") (class "Default")
      (node (ref "C8") (pin "2") (pinfunction "2_2") (pintype "passive"))
      (node (ref "R2") (pin "1") (pinfunction "1_1") (pintype "passive"))
      (node (ref "R3") (pin "2") (pinfunction "2_2") (pintype "passive"))
    )
    (net (code "94") (name "POR_B") (class "Default")
      (node (ref "R2") (pin "2") (pinfunction "2_2") (pintype "passive"))
    )
    (net (code "95") (name "SW2_1V8") (class "Default")
      (node (ref "C1") (pin "2") (pinfunction "2_2") (pintype "passive"))
      (node (ref "U1") (pin "20") (pinfunction "VDDD_20") (pintype "power_in"))
    )
    (net (code "96") (name "USER_BP0") (class "Default")
      (node (ref "S3") (pin "3") (pinfunction "3_3") (pintype "passive"))
      (node (ref "S3") (pin "4") (pinfunction "4_4") (pintype "passive"))
    )
    (net (code "97") (name "USER_BP1") (class "Default")
      (node (ref "S4") (pin "3") (pinfunction "3_3") (pintype "passive"))
      (node (ref "S4") (pin "4") (pinfunction "4_4") (pintype "passive"))
    )
    (net (code "98") (name "USER_BP2") (class "Default")
      (node (ref "S5") (pin "3") (pinfunction "3_3") (pintype "passive"))
      (node (ref "S5") (pin "4") (pinfunction "4_4") (pintype "passive"))
    )
    (net (code "99") (name "USER_BP3") (class "Default")
      (node (ref "S6") (pin "3") (pinfunction "3_3") (pintype "passive"))
      (node (ref "S6") (pin "4") (pinfunction "4_4") (pintype "passive"))
    )
    (net (code "100") (name "USER_BP4") (class "Default")
      (node (ref "S7") (pin "3") (pinfunction "3_3") (pintype "passive"))
      (node (ref "S7") (pin "4") (pinfunction "4_4") (pintype "passive"))
    )
    (net (code "101") (name "USER_BP5") (class "Default")
      (node (ref "S8") (pin "3") (pinfunction "3_3") (pintype "passive"))
      (node (ref "S8") (pin "4") (pinfunction "4_4") (pintype "passive"))
    )
    (net (code "102") (name "USER_BP6") (class "Default")
      (node (ref "S9") (pin "3") (pinfunction "3_3") (pintype "passive"))
      (node (ref "S9") (pin "4") (pinfunction "4_4") (pintype "passive"))
    )
    (net (code "103") (name "USER_BP7") (class "Default")
      (node (ref "S10") (pin "3") (pinfunction "3_3") (pintype "passive"))
      (node (ref "S10") (pin "4") (pinfunction "4_4") (pintype "passive"))
    )
    (net (code "104") (name "USER_LED_0") (class "Default")
      (node (ref "D2") (pin "2") (pinfunction "K_2") (pintype "passive"))
    )
    (net (code "105") (name "USER_LED_1") (class "Default")
      (node (ref "D3") (pin "2") (pinfunction "K_2") (pintype "passive"))
    )
    (net (code "106") (name "USER_LED_2") (class "Default")
      (node (ref "D4") (pin "2") (pinfunction "K_2") (pintype "passive"))
    )
    (net (code "107") (name "USER_LED_3") (class "Default")
      (node (ref "D5") (pin "2") (pinfunction "K_2") (pintype "passive"))
    )
    (net (code "108") (name "USER_LED_4") (class "Default")
      (node (ref "D6") (pin "2") (pinfunction "K_2") (pintype "passive"))
    )
    (net (code "109") (name "USER_LED_5") (class "Default")
      (node (ref "D7") (pin "2") (pinfunction "K_2") (pintype "passive"))
    )
    (net (code "110") (name "USER_LED_6") (class "Default")
      (node (ref "D8") (pin "2") (pinfunction "K_2") (pintype "passive"))
    )
    (net (code "111") (name "USER_LED_7") (class "Default")
      (node (ref "D9") (pin "2") (pinfunction "K_2") (pintype "passive"))
    )
    (net (code "112") (name "USER_LED_8") (class "Default")
      (node (ref "D1") (pin "20") (pinfunction "20_20") (pintype "passive"))
    )
    (net (code "113") (name "USER_LED_9") (class "Default")
      (node (ref "D1") (pin "19") (pinfunction "19_19") (pintype "passive"))
    )
    (net (code "114") (name "USER_LED_10") (class "Default")
      (node (ref "D1") (pin "18") (pinfunction "18_18") (pintype "passive"))
    )
    (net (code "115") (name "USER_LED_11") (class "Default")
      (node (ref "D1") (pin "17") (pinfunction "17_17") (pintype "passive"))
    )
    (net (code "116") (name "USER_LED_12") (class "Default")
      (node (ref "D1") (pin "16") (pinfunction "16_16") (pintype "passive"))
    )
    (net (code "117") (name "USER_LED_13") (class "Default")
      (node (ref "D1") (pin "15") (pinfunction "15_15") (pintype "passive"))
    )
    (net (code "118") (name "USER_LED_14") (class "Default")
      (node (ref "D1") (pin "14") (pinfunction "14_14") (pintype "passive"))
    )
    (net (code "119") (name "USER_LED_15") (class "Default")
      (node (ref "D1") (pin "13") (pinfunction "13_13") (pintype "passive"))
    )
    (net (code "120") (name "USER_LED_16") (class "Default")
      (node (ref "D1") (pin "12") (pinfunction "12_12") (pintype "passive"))
    )
    (net (code "121") (name "USER_LED_17") (class "Default")
      (node (ref "D1") (pin "11") (pinfunction "11_11") (pintype "passive"))
    )
    (net (code "122") (name "unconnected-(J1-Pad16)") (class "Default")
      (node (ref "J1") (pin "16") (pinfunction "16_16") (pintype "passive+no_connect"))
    )
    (net (code "123") (name "unconnected-(J1-Pad17)") (class "Default")
      (node (ref "J1") (pin "17") (pinfunction "17_17") (pintype "passive+no_connect"))
    )
    (net (code "124") (name "unconnected-(J1-Pad18)") (class "Default")
      (node (ref "J1") (pin "18") (pinfunction "18_18") (pintype "passive+no_connect"))
    )
    (net (code "125") (name "unconnected-(J1-Pad19)") (class "Default")
      (node (ref "J1") (pin "19") (pinfunction "19_19") (pintype "passive+no_connect"))
    )
    (net (code "126") (name "unconnected-(J1-Pad20)") (class "Default")
      (node (ref "J1") (pin "20") (pinfunction "20_20") (pintype "passive+no_connect"))
    )
    (net (code "127") (name "unconnected-(J1-Pad21)") (class "Default")
      (node (ref "J1") (pin "21") (pinfunction "21_21") (pintype "passive+no_connect"))
    )
    (net (code "128") (name "unconnected-(J1-Pad22)") (class "Default")
      (node (ref "J1") (pin "22") (pinfunction "22_22") (pintype "passive+no_connect"))
    )
    (net (code "129") (name "unconnected-(J1-Pad23)") (class "Default")
      (node (ref "J1") (pin "23") (pinfunction "23_23") (pintype "passive+no_connect"))
    )
    (net (code "130") (name "unconnected-(J1-Pad24)") (class "Default")
      (node (ref "J1") (pin "24") (pinfunction "24_24") (pintype "passive+no_connect"))
    )
    (net (code "131") (name "unconnected-(J1-Pad25)") (class "Default")
      (node (ref "J1") (pin "25") (pinfunction "25_25") (pintype "passive+no_connect"))
    )
    (net (code "132") (name "unconnected-(J1-Pad26)") (class "Default")
      (node (ref "J1") (pin "26") (pinfunction "26_26") (pintype "passive+no_connect"))
    )
    (net (code "133") (name "unconnected-(J1-Pad27)") (class "Default")
      (node (ref "J1") (pin "27") (pinfunction "27_27") (pintype "passive+no_connect"))
    )
    (net (code "134") (name "unconnected-(J1-Pad28)") (class "Default")
      (node (ref "J1") (pin "28") (pinfunction "28_28") (pintype "passive+no_connect"))
    )
    (net (code "135") (name "unconnected-(J1-Pad29)") (class "Default")
      (node (ref "J1") (pin "29") (pinfunction "29_29") (pintype "passive+no_connect"))
    )
    (net (code "136") (name "unconnected-(J1-Pad30)") (class "Default")
      (node (ref "J1") (pin "30") (pinfunction "30_30") (pintype "passive+no_connect"))
    )
    (net (code "137") (name "unconnected-(J2-Pad16)") (class "Default")
      (node (ref "J2") (pin "16") (pinfunction "16_16") (pintype "passive+no_connect"))
    )
    (net (code "138") (name "unconnected-(J2-Pad17)") (class "Default")
      (node (ref "J2") (pin "17") (pinfunction "17_17") (pintype "passive+no_connect"))
    )
    (net (code "139") (name "unconnected-(J2-Pad18)") (class "Default")
      (node (ref "J2") (pin "18") (pinfunction "18_18") (pintype "passive+no_connect"))
    )
    (net (code "140") (name "unconnected-(J2-Pad19)") (class "Default")
      (node (ref "J2") (pin "19") (pinfunction "19_19") (pintype "passive+no_connect"))
    )
    (net (code "141") (name "unconnected-(J2-Pad20)") (class "Default")
      (node (ref "J2") (pin "20") (pinfunction "20_20") (pintype "passive+no_connect"))
    )
    (net (code "142") (name "unconnected-(J2-Pad21)") (class "Default")
      (node (ref "J2") (pin "21") (pinfunction "21_21") (pintype "passive+no_connect"))
    )
    (net (code "143") (name "unconnected-(J2-Pad22)") (class "Default")
      (node (ref "J2") (pin "22") (pinfunction "22_22") (pintype "passive+no_connect"))
    )
    (net (code "144") (name "unconnected-(J2-Pad23)") (class "Default")
      (node (ref "J2") (pin "23") (pinfunction "23_23") (pintype "passive+no_connect"))
    )
    (net (code "145") (name "unconnected-(J2-Pad24)") (class "Default")
      (node (ref "J2") (pin "24") (pinfunction "24_24") (pintype "passive+no_connect"))
    )
    (net (code "146") (name "unconnected-(J2-Pad25)") (class "Default")
      (node (ref "J2") (pin "25") (pinfunction "25_25") (pintype "passive+no_connect"))
    )
    (net (code "147") (name "unconnected-(J2-Pad26)") (class "Default")
      (node (ref "J2") (pin "26") (pinfunction "26_26") (pintype "passive+no_connect"))
    )
    (net (code "148") (name "unconnected-(J2-Pad27)") (class "Default")
      (node (ref "J2") (pin "27") (pinfunction "27_27") (pintype "passive+no_connect"))
    )
    (net (code "149") (name "unconnected-(J2-Pad28)") (class "Default")
      (node (ref "J2") (pin "28") (pinfunction "28_28") (pintype "passive+no_connect"))
    )
    (net (code "150") (name "unconnected-(J2-Pad29)") (class "Default")
      (node (ref "J2") (pin "29") (pinfunction "29_29") (pintype "passive+no_connect"))
    )
    (net (code "151") (name "unconnected-(J2-Pad30)") (class "Default")
      (node (ref "J2") (pin "30") (pinfunction "30_30") (pintype "passive+no_connect"))
    )
    (net (code "152") (name "unconnected-(J3-Pad5)") (class "Default")
      (node (ref "J3") (pin "5") (pintype "passive+no_connect"))
    )
    (net (code "153") (name "unconnected-(J3-Pad6)") (class "Default")
      (node (ref "J3") (pin "6") (pintype "passive+no_connect"))
    )
    (net (code "154") (name "unconnected-(R4-Pad1)") (class "Default")
      (node (ref "R4") (pin "1") (pinfunction "1_1") (pintype "passive+no_connect"))
    )
    (net (code "155") (name "unconnected-(R4-Pad8)") (class "Default")
      (node (ref "R4") (pin "8") (pinfunction "8_8") (pintype "passive+no_connect"))
    )
    (net (code "156") (name "unconnected-(R6-Pad4)") (class "Default")
      (node (ref "R6") (pin "4") (pinfunction "4_4") (pintype "passive+no_connect"))
    )
    (net (code "157") (name "unconnected-(R6-Pad5)") (class "Default")
      (node (ref "R6") (pin "5") (pinfunction "5_5") (pintype "passive+no_connect"))
    )
    (net (code "158") (name "unconnected-(U1-HP_VGND-Pad2)") (class "Default")
      (node (ref "U1") (pin "2") (pinfunction "HP_VGND_2") (pintype "power_in+no_connect"))
    )
    (net (code "159") (name "unconnected-(U1-LINEIN_L-Pad9)") (class "Default")
      (node (ref "U1") (pin "9") (pinfunction "LINEIN_L_9") (pintype "input+no_connect"))
    )
    (net (code "160") (name "unconnected-(U1-LINEIN_R-Pad8)") (class "Default")
      (node (ref "U1") (pin "8") (pinfunction "LINEIN_R_8") (pintype "input+no_connect"))
    )
    (net (code "161") (name "unconnected-(U1-LINEOUT_L-Pad7)") (class "Default")
      (node (ref "U1") (pin "7") (pinfunction "LINEOUT_L_7") (pintype "output+no_connect"))
    )
    (net (code "162") (name "unconnected-(U1-LINEOUT_R-Pad6)") (class "Default")
      (node (ref "U1") (pin "6") (pinfunction "LINEOUT_R_6") (pintype "output+no_connect"))
    )
  )
)
